# analyze_remocon.net
KiCad netlist of a schematic drawn in EAGLE
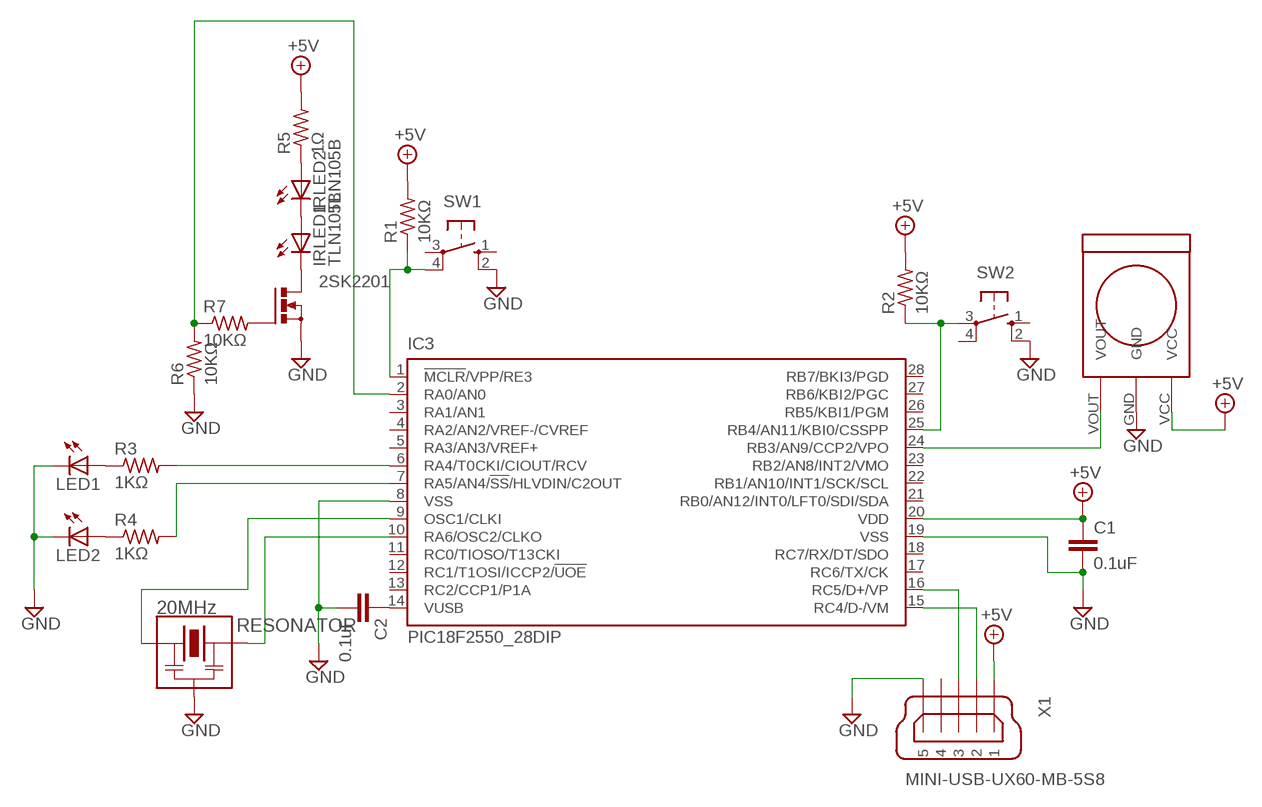
[diagram p0: schematic, sheet 1]

(export (version "E")
  (design (tool "Eeschema 10.0.6"))
  (components
    (comp (ref "2SK2201")
      (value "BUZ11BV")
      (footprint "eagle-import:TO220BV")
      (libsource (lib "eagle-import") (part "BUZ11BV"))
    )
    (comp (ref "C1")
      (value "0.1uF")
      (footprint "eagle-import:C025-024X044")
      (libsource (lib "eagle-import") (part "C-EU025-024X044"))
    )
    (comp (ref "C2")
      (value "0.1uF")
      (footprint "eagle-import:C025-024X044")
      (libsource (lib "eagle-import") (part "C-EU025-024X044"))
    )
    (comp (ref "IC3")
      (value "PIC18F2550_28DIP")
      (footprint "eagle-import:DIL28-3")
      (fields (field (name "MF") "MICROCHIP") (field (name "MPN") "PIC18F2550-I/SP"))
      (libsource (lib "eagle-import") (part "PIC18F2_28DIP550"))
    )
    (comp (ref "IRLED1")
      (value "TLN105B")
      (footprint "eagle-import:LED3MM")
      (libsource (lib "eagle-import") (part "LED3MM"))
    )
    (comp (ref "IRLED2")
      (value "TLN105B")
      (footprint "eagle-import:LED3MM")
      (libsource (lib "eagle-import") (part "LED3MM"))
    )
    (comp (ref "LED1")
      (value "LED3MM")
      (footprint "eagle-import:LED3MM")
      (libsource (lib "eagle-import") (part "LED3MM"))
    )
    (comp (ref "LED2")
      (value "LED3MM")
      (footprint "eagle-import:LED3MM")
      (libsource (lib "eagle-import") (part "LED3MM"))
    )
    (comp (ref "PL-IRM2161-C438")
      (value "IRM2161")
      (footprint "eagle-import:PL-IRM2161-C438")
      (libsource (lib "eagle-import") (part "IRM2161"))
    )
    (comp (ref "R1")
      (value "10KΩ")
      (footprint "eagle-import:MINI_MELF-0102R")
      (libsource (lib "eagle-import") (part "R-US_MELF0102R"))
    )
    (comp (ref "R2")
      (value "10KΩ")
      (footprint "eagle-import:MINI_MELF-0102R")
      (libsource (lib "eagle-import") (part "R-US_MELF0102R"))
    )
    (comp (ref "R3")
      (value "1KΩ")
      (footprint "eagle-import:MINI_MELF-0102R")
      (libsource (lib "eagle-import") (part "R-US_MELF0102R"))
    )
    (comp (ref "R4")
      (value "1KΩ")
      (footprint "eagle-import:MINI_MELF-0102R")
      (libsource (lib "eagle-import") (part "R-US_MELF0102R"))
    )
    (comp (ref "R5")
      (value "1Ω")
      (footprint "eagle-import:0207_7")
      (libsource (lib "eagle-import") (part "R-US_0207/7"))
    )
    (comp (ref "R6")
      (value "10KΩ")
      (footprint "eagle-import:0207_7")
      (libsource (lib "eagle-import") (part "R-US_0207/7"))
    )
    (comp (ref "R7")
      (value "10KΩ")
      (footprint "eagle-import:0207_7")
      (libsource (lib "eagle-import") (part "R-US_0207/7"))
    )
    (comp (ref "RESONATOR")
      (value "20MHz")
      (footprint "eagle-import:HC-49G")
      (libsource (lib "eagle-import") (part "CRES-HA"))
    )
    (comp (ref "SW1")
      (value "10-XX")
      (footprint "eagle-import:B3F-10XX")
      (fields (field (name "MPN") "B3F-1000"))
      (libsource (lib "eagle-import") (part "10-XX"))
    )
    (comp (ref "SW2")
      (value "10-XX")
      (footprint "eagle-import:B3F-10XX")
      (fields (field (name "MPN") "B3F-1000"))
      (libsource (lib "eagle-import") (part "10-XX"))
    )
    (comp (ref "X1")
      (value "MINI-USB-UX60-MB-5S8")
      (footprint "eagle-import:UX60-MB-5S8")
      (libsource (lib "eagle-import") (part "MINI-USB-UX60-MB-5S8"))
    )
  )
  (nets
    (net (code "1") (name "+5V") (class "Default")
      (node (ref "C1") (pin "1") (pinfunction "1_1") (pintype "passive"))
      (node (ref "IC3") (pin "20") (pinfunction "VDD_20") (pintype "power_in"))
      (node (ref "PL-IRM2161-C438") (pin "VCC") (pinfunction "VCC_VCC") (pintype "bidirectional"))
      (node (ref "R1") (pin "2") (pinfunction "2_2") (pintype "passive"))
      (node (ref "R2") (pin "2") (pinfunction "2_2") (pintype "passive"))
      (node (ref "R5") (pin "2") (pinfunction "2_2") (pintype "passive"))
      (node (ref "X1") (pin "1") (pinfunction "1_1") (pintype "input"))
    )
    (net (code "2") (name "GND") (class "Default")
      (node (ref "2SK2201") (pin "S") (pinfunction "S_S") (pintype "passive"))
      (node (ref "C1") (pin "2") (pinfunction "2_2") (pintype "passive"))
      (node (ref "C2") (pin "2") (pinfunction "2_2") (pintype "passive"))
      (node (ref "IC3") (pin "19") (pinfunction "VSS_19") (pintype "power_in"))
      (node (ref "IC3") (pin "8") (pinfunction "VSS_8") (pintype "power_in"))
      (node (ref "LED1") (pin "K") (pinfunction "C_K") (pintype "passive"))
      (node (ref "LED2") (pin "K") (pinfunction "C_K") (pintype "passive"))
      (node (ref "PL-IRM2161-C438") (pin "GND") (pinfunction "GND_GND") (pintype "bidirectional"))
      (node (ref "R6") (pin "1") (pinfunction "1_1") (pintype "passive"))
      (node (ref "RESONATOR") (pin "CENT") (pinfunction "GND_CENT") (pintype "bidirectional"))
      (node (ref "SW1") (pin "2") (pinfunction "S1_2") (pintype "passive"))
      (node (ref "SW2") (pin "2") (pinfunction "S1_2") (pintype "passive"))
      (node (ref "X1") (pin "5") (pinfunction "5_5") (pintype "input"))
    )
    (net (code "3") (name "Net-(2SK2201-PadG)") (class "Default")
      (node (ref "2SK2201") (pin "G") (pinfunction "G_G") (pintype "passive"))
      (node (ref "R7") (pin "2") (pinfunction "2_2") (pintype "passive"))
    )
    (net (code "4") (name "Net-(IC3-OSC1{slash}CLKI)") (class "Default")
      (node (ref "IC3") (pin "9") (pinfunction "OSC1/CLKI_9") (pintype "input"))
      (node (ref "RESONATOR") (pin "P1") (pinfunction "LFT_P1") (pintype "bidirectional"))
    )
    (net (code "5") (name "Net-(IC3-RA0{slash}AN0)") (class "Default")
      (node (ref "IC3") (pin "2") (pinfunction "RA0/AN0_2") (pintype "bidirectional"))
      (node (ref "R6") (pin "2") (pinfunction "2_2") (pintype "passive"))
      (node (ref "R7") (pin "1") (pinfunction "1_1") (pintype "passive"))
    )
    (net (code "6") (name "Net-(IC3-RA4{slash}T0CKI{slash}CIOUT{slash}RCV)") (class "Default")
      (node (ref "IC3") (pin "6") (pinfunction "RA4/T0CKI/CIOUT/RCV_6") (pintype "bidirectional"))
      (node (ref "R3") (pin "2") (pinfunction "2_2") (pintype "passive"))
    )
    (net (code "7") (name "Net-(IC3-RA5{slash}AN4{slash}~{SS}{slash}HLVDIN{slash}C2OUT)") (class "Default")
      (node (ref "IC3") (pin "7") (pinfunction "RA5/AN4/~{SS}/HLVDIN/C2OUT_7") (pintype "bidirectional"))
      (node (ref "R4") (pin "2") (pinfunction "2_2") (pintype "passive"))
    )
    (net (code "8") (name "Net-(IC3-RA6{slash}OSC2{slash}CLKO)") (class "Default")
      (node (ref "IC3") (pin "10") (pinfunction "RA6/OSC2/CLKO_10") (pintype "output"))
      (node (ref "RESONATOR") (pin "P2") (pinfunction "RIT_P2") (pintype "bidirectional"))
    )
    (net (code "9") (name "Net-(IC3-RB3{slash}AN9{slash}CCP2{slash}VPO)") (class "Default")
      (node (ref "IC3") (pin "24") (pinfunction "RB3/AN9/CCP2/VPO_24") (pintype "bidirectional"))
      (node (ref "PL-IRM2161-C438") (pin "VOUT") (pinfunction "VOUT_VOUT") (pintype "bidirectional"))
    )
    (net (code "10") (name "Net-(IC3-RB4{slash}AN11{slash}KBI0{slash}CSSPP)") (class "Default")
      (node (ref "IC3") (pin "25") (pinfunction "RB4/AN11/KBI0/CSSPP_25") (pintype "bidirectional"))
      (node (ref "R2") (pin "1") (pinfunction "1_1") (pintype "passive"))
      (node (ref "SW2") (pin "3") (pinfunction "P_3") (pintype "passive"))
    )
    (net (code "11") (name "Net-(IC3-RC4{slash}D-{slash}VM)") (class "Default")
      (node (ref "IC3") (pin "15") (pinfunction "RC4/D-/VM_15") (pintype "bidirectional"))
      (node (ref "X1") (pin "2") (pinfunction "2_2") (pintype "input"))
    )
    (net (code "12") (name "Net-(IC3-RC5{slash}D+{slash}VP)") (class "Default")
      (node (ref "IC3") (pin "16") (pinfunction "RC5/D+/VP_16") (pintype "bidirectional"))
      (node (ref "X1") (pin "3") (pinfunction "3_3") (pintype "input"))
    )
    (net (code "13") (name "Net-(IC3-VUSB)") (class "Default")
      (node (ref "C2") (pin "1") (pinfunction "1_1") (pintype "passive"))
      (node (ref "IC3") (pin "14") (pinfunction "VUSB_14") (pintype "bidirectional"))
    )
    (net (code "14") (name "Net-(IC3-~{MCLR}{slash}VPP{slash}RE3)") (class "Default")
      (node (ref "IC3") (pin "1") (pinfunction "~{MCLR}/VPP/RE3_1") (pintype "input"))
      (node (ref "R1") (pin "1") (pinfunction "1_1") (pintype "passive"))
      (node (ref "SW1") (pin "4") (pinfunction "P1_4") (pintype "passive"))
    )
    (net (code "15") (name "Net-(IRLED1-C)") (class "Default")
      (node (ref "2SK2201") (pin "D") (pinfunction "D_D") (pintype "passive"))
      (node (ref "IRLED1") (pin "K") (pinfunction "C_K") (pintype "passive"))
    )
    (net (code "16") (name "Net-(IRLED2-C)") (class "Default")
      (node (ref "IRLED1") (pin "A") (pinfunction "A_A") (pintype "passive"))
      (node (ref "IRLED2") (pin "K") (pinfunction "C_K") (pintype "passive"))
    )
    (net (code "17") (name "Net-(IRLED2-PadA)") (class "Default")
      (node (ref "IRLED2") (pin "A") (pinfunction "A_A") (pintype "passive"))
      (node (ref "R5") (pin "1") (pinfunction "1_1") (pintype "passive"))
    )
    (net (code "18") (name "Net-(LED1-PadA)") (class "Default")
      (node (ref "LED1") (pin "A") (pinfunction "A_A") (pintype "passive"))
      (node (ref "R3") (pin "1") (pinfunction "1_1") (pintype "passive"))
    )
    (net (code "19") (name "Net-(LED2-PadA)") (class "Default")
      (node (ref "LED2") (pin "A") (pinfunction "A_A") (pintype "passive"))
      (node (ref "R4") (pin "1") (pinfunction "1_1") (pintype "passive"))
    )
    (net (code "20") (name "unconnected-(IC3-RA1{slash}AN1-Pad3)") (class "Default")
      (node (ref "IC3") (pin "3") (pinfunction "RA1/AN1_3") (pintype "bidirectional"))
    )
    (net (code "21") (name "unconnected-(IC3-RA2{slash}AN2{slash}VREF-{slash}CVREF-Pad4)") (class "Default")
      (node (ref "IC3") (pin "4") (pinfunction "RA2/AN2/VREF-/CVREF_4") (pintype "bidirectional"))
    )
    (net (code "22") (name "unconnected-(IC3-RA3{slash}AN3{slash}VREF+-Pad5)") (class "Default")
      (node (ref "IC3") (pin "5") (pinfunction "RA3/AN3/VREF+_5") (pintype "bidirectional"))
    )
    (net (code "23") (name "unconnected-(IC3-RB0{slash}AN12{slash}INT0{slash}LFT0{slash}SDI{slash}SDA-Pad21)") (class "Default")
      (node (ref "IC3") (pin "21") (pinfunction "RB0/AN12/INT0/LFT0/SDI/SDA_21") (pintype "bidirectional"))
    )
    (net (code "24") (name "unconnected-(IC3-RB1{slash}AN10{slash}INT1{slash}SCK{slash}SCL-Pad22)") (class "Default")
      (node (ref "IC3") (pin "22") (pinfunction "RB1/AN10/INT1/SCK/SCL_22") (pintype "bidirectional"))
    )
    (net (code "25") (name "unconnected-(IC3-RB2{slash}AN8{slash}INT2{slash}VMO-Pad23)") (class "Default")
      (node (ref "IC3") (pin "23") (pinfunction "RB2/AN8/INT2/VMO_23") (pintype "bidirectional"))
    )
    (net (code "26") (name "unconnected-(IC3-RB5{slash}KBI1{slash}PGM-Pad26)") (class "Default")
      (node (ref "IC3") (pin "26") (pinfunction "RB5/KBI1/PGM_26") (pintype "bidirectional"))
    )
    (net (code "27") (name "unconnected-(IC3-RB6{slash}KBI2{slash}PGC-Pad27)") (class "Default")
      (node (ref "IC3") (pin "27") (pinfunction "RB6/KBI2/PGC_27") (pintype "bidirectional"))
    )
    (net (code "28") (name "unconnected-(IC3-RB7{slash}BKI3{slash}PGD-Pad28)") (class "Default")
      (node (ref "IC3") (pin "28") (pinfunction "RB7/BKI3/PGD_28") (pintype "bidirectional"))
    )
    (net (code "29") (name "unconnected-(IC3-RC0{slash}TIOSO{slash}T13CKI-Pad11)") (class "Default")
      (node (ref "IC3") (pin "11") (pinfunction "RC0/TIOSO/T13CKI_11") (pintype "bidirectional"))
    )
    (net (code "30") (name "unconnected-(IC3-RC1{slash}T1OSI{slash}ICCP2{slash}~{UOE}-Pad12)") (class "Default")
      (node (ref "IC3") (pin "12") (pinfunction "RC1/T1OSI/ICCP2/~{UOE}_12") (pintype "bidirectional"))
    )
    (net (code "31") (name "unconnected-(IC3-RC2{slash}CCP1{slash}P1A-Pad13)") (class "Default")
      (node (ref "IC3") (pin "13") (pinfunction "RC2/CCP1/P1A_13") (pintype "bidirectional"))
    )
    (net (code "32") (name "unconnected-(IC3-RC6{slash}TX{slash}CK-Pad17)") (class "Default")
      (node (ref "IC3") (pin "17") (pinfunction "RC6/TX/CK_17") (pintype "bidirectional"))
    )
    (net (code "33") (name "unconnected-(IC3-RC7{slash}RX{slash}DT{slash}SDO-Pad18)") (class "Default")
      (node (ref "IC3") (pin "18") (pinfunction "RC7/RX/DT/SDO_18") (pintype "bidirectional"))
    )
    (net (code "34") (name "unconnected-(SW1-P-Pad3)") (class "Default")
      (node (ref "SW1") (pin "3") (pinfunction "P_3") (pintype "passive"))
    )
    (net (code "35") (name "unconnected-(SW1-S-Pad1)") (class "Default")
      (node (ref "SW1") (pin "1") (pinfunction "S_1") (pintype "passive"))
    )
    (net (code "36") (name "unconnected-(SW2-P1-Pad4)") (class "Default")
      (node (ref "SW2") (pin "4") (pinfunction "P1_4") (pintype "passive"))
    )
    (net (code "37") (name "unconnected-(SW2-S-Pad1)") (class "Default")
      (node (ref "SW2") (pin "1") (pinfunction "S_1") (pintype "passive"))
    )
    (net (code "38") (name "unconnected-(X1-Pad4)") (class "Default")
      (node (ref "X1") (pin "4") (pinfunction "4_4") (pintype "input"))
    )
  )
)
